# untitled.net
KiCad netlist of a schematic drawn in EAGLE
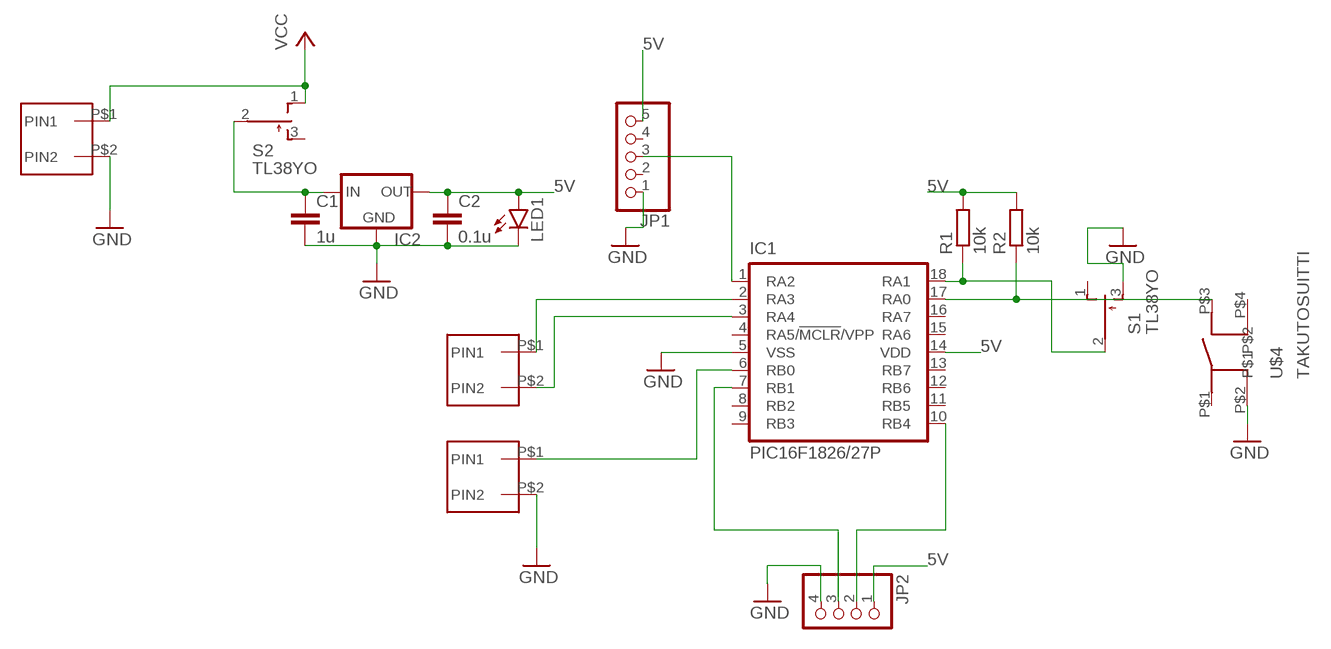
[diagram p0: schematic, sheet 1]

(export (version "E")
  (design (tool "Eeschema 10.0.6"))
  (components
    (comp (ref "C1")
      (value "1u")
      (footprint "eagle-import:C025-025X050")
      (libsource (lib "eagle-import") (part "C-EU025-025X050"))
    )
    (comp (ref "C2")
      (value "0.1u")
      (footprint "eagle-import:C025-025X050")
      (libsource (lib "eagle-import") (part "C-EU025-025X050"))
    )
    (comp (ref "IC1")
      (value "PIC16F1826/27P")
      (footprint "eagle-import:DIL18")
      (libsource (lib "eagle-import") (part "PIC16F1826/27P"))
    )
    (comp (ref "IC2")
      (value "78XXS")
      (footprint "eagle-import:78XXS")
      (libsource (lib "eagle-import") (part "78XXS"))
    )
    (comp (ref "JP1")
      (value "PINHD-1X5")
      (footprint "eagle-import:1X05")
      (libsource (lib "eagle-import") (part "PINHD-1X5"))
    )
    (comp (ref "JP2")
      (value "PINHD-1X4")
      (footprint "eagle-import:1X04")
      (libsource (lib "eagle-import") (part "PINHD-1X4"))
    )
    (comp (ref "LED1")
      (value "LED5MM")
      (footprint "eagle-import:LED5MM")
      (libsource (lib "eagle-import") (part "LED5MM"))
    )
    (comp (ref "R1")
      (value "10k")
      (footprint "eagle-import:0207_10")
      (libsource (lib "eagle-import") (part "R-EU_0207/10"))
    )
    (comp (ref "R2")
      (value "10k")
      (footprint "eagle-import:0207_10")
      (libsource (lib "eagle-import") (part "R-EU_0207/10"))
    )
    (comp (ref "S1")
      (value "TL38YO")
      (footprint "eagle-import:TL3XYO")
      (libsource (lib "eagle-import") (part "TL38YO"))
    )
    (comp (ref "S2")
      (value "TL38YO")
      (footprint "eagle-import:TL3XYO")
      (libsource (lib "eagle-import") (part "TL38YO"))
    )
    (comp (ref "U$1")
      (value "TERMINAL_2")
      (footprint "eagle-import:TERMINAL_2")
      (libsource (lib "eagle-import") (part "TERMINAL_2"))
    )
    (comp (ref "U$2")
      (value "TERMINAL_2")
      (footprint "eagle-import:TERMINAL_2")
      (libsource (lib "eagle-import") (part "TERMINAL_2"))
    )
    (comp (ref "U$3")
      (value "TERMINAL_2")
      (footprint "eagle-import:TERMINAL_2")
      (libsource (lib "eagle-import") (part "TERMINAL_2"))
    )
    (comp (ref "U$4")
      (value "TAKUTOSUITTI")
      (footprint "eagle-import:TAKUTOSUITTI")
      (libsource (lib "eagle-import") (part "TAKUTOSUITTI"))
    )
  )
  (nets
    (net (code "1") (name "/5V") (class "Default")
      (node (ref "C2") (pin "1") (pinfunction "1_1") (pintype "passive"))
      (node (ref "IC1") (pin "14") (pinfunction "VDD_14") (pintype "power_in"))
      (node (ref "IC2") (pin "OUT") (pinfunction "OUT_OUT") (pintype "passive"))
      (node (ref "JP1") (pin "5") (pinfunction "5_5") (pintype "passive"))
      (node (ref "JP2") (pin "1") (pinfunction "1_1") (pintype "passive"))
      (node (ref "LED1") (pin "A") (pinfunction "A_A") (pintype "passive"))
      (node (ref "R1") (pin "2") (pinfunction "2_2") (pintype "passive"))
      (node (ref "R2") (pin "2") (pinfunction "2_2") (pintype "passive"))
    )
    (net (code "2") (name "GND") (class "Default")
      (node (ref "C1") (pin "2") (pinfunction "2_2") (pintype "passive"))
      (node (ref "C2") (pin "2") (pinfunction "2_2") (pintype "passive"))
      (node (ref "IC1") (pin "5") (pinfunction "VSS_5") (pintype "power_in"))
      (node (ref "IC2") (pin "GND") (pinfunction "GND_GND") (pintype "input"))
      (node (ref "JP1") (pin "1") (pinfunction "1_1") (pintype "passive"))
      (node (ref "JP2") (pin "4") (pinfunction "4_4") (pintype "passive"))
      (node (ref "LED1") (pin "K") (pinfunction "C_K") (pintype "passive"))
      (node (ref "S1") (pin "3") (pinfunction "S_3") (pintype "passive"))
      (node (ref "U$1") (pin "P$2") (pinfunction "PIN2_P$2") (pintype "bidirectional"))
      (node (ref "U$3") (pin "P$2") (pinfunction "PIN2_P$2") (pintype "bidirectional"))
      (node (ref "U$4") (pin "P$2") (pinfunction "P$2_P$2") (pintype "bidirectional"))
    )
    (net (code "3") (name "Net-(IC1-RA0)") (class "Default")
      (node (ref "IC1") (pin "17") (pinfunction "RA0_17") (pintype "bidirectional"))
      (node (ref "R2") (pin "1") (pinfunction "1_1") (pintype "passive"))
      (node (ref "U$4") (pin "P$3") (pinfunction "S_P$3") (pintype "passive"))
    )
    (net (code "4") (name "Net-(IC1-RA1)") (class "Default")
      (node (ref "IC1") (pin "18") (pinfunction "RA1_18") (pintype "bidirectional"))
      (node (ref "R1") (pin "1") (pinfunction "1_1") (pintype "passive"))
      (node (ref "S1") (pin "2") (pinfunction "P_2") (pintype "passive"))
    )
    (net (code "5") (name "Net-(IC1-RA2)") (class "Default")
      (node (ref "IC1") (pin "1") (pinfunction "RA2_1") (pintype "bidirectional"))
      (node (ref "JP1") (pin "3") (pinfunction "3_3") (pintype "passive"))
    )
    (net (code "6") (name "Net-(IC1-RA3)") (class "Default")
      (node (ref "IC1") (pin "2") (pinfunction "RA3_2") (pintype "bidirectional"))
      (node (ref "U$2") (pin "P$1") (pinfunction "PIN1_P$1") (pintype "bidirectional"))
    )
    (net (code "7") (name "Net-(IC1-RA4)") (class "Default")
      (node (ref "IC1") (pin "3") (pinfunction "RA4_3") (pintype "bidirectional"))
      (node (ref "U$2") (pin "P$2") (pinfunction "PIN2_P$2") (pintype "bidirectional"))
    )
    (net (code "8") (name "Net-(IC1-RB0)") (class "Default")
      (node (ref "IC1") (pin "6") (pinfunction "RB0_6") (pintype "bidirectional"))
      (node (ref "U$3") (pin "P$1") (pinfunction "PIN1_P$1") (pintype "bidirectional"))
    )
    (net (code "9") (name "Net-(IC1-RB1)") (class "Default")
      (node (ref "IC1") (pin "7") (pinfunction "RB1_7") (pintype "bidirectional"))
      (node (ref "JP2") (pin "3") (pinfunction "3_3") (pintype "passive"))
    )
    (net (code "10") (name "Net-(IC1-RB4)") (class "Default")
      (node (ref "IC1") (pin "10") (pinfunction "RB4_10") (pintype "bidirectional"))
      (node (ref "JP2") (pin "2") (pinfunction "2_2") (pintype "passive"))
    )
    (net (code "11") (name "Net-(S2-P)") (class "Default")
      (node (ref "C1") (pin "1") (pinfunction "1_1") (pintype "passive"))
      (node (ref "IC2") (pin "IN") (pinfunction "IN_IN") (pintype "input"))
      (node (ref "S2") (pin "2") (pinfunction "P_2") (pintype "passive"))
    )
    (net (code "12") (name "VCC") (class "Default")
      (node (ref "S2") (pin "1") (pinfunction "O_1") (pintype "passive"))
      (node (ref "U$1") (pin "P$1") (pinfunction "PIN1_P$1") (pintype "bidirectional"))
    )
    (net (code "13") (name "unconnected-(IC1-RA5{slash}~{MCLR}{slash}VPP-Pad4)") (class "Default")
      (node (ref "IC1") (pin "4") (pinfunction "RA5/~{MCLR}/VPP_4") (pintype "bidirectional"))
    )
    (net (code "14") (name "unconnected-(IC1-RA6-Pad15)") (class "Default")
      (node (ref "IC1") (pin "15") (pinfunction "RA6_15") (pintype "bidirectional"))
    )
    (net (code "15") (name "unconnected-(IC1-RA7-Pad16)") (class "Default")
      (node (ref "IC1") (pin "16") (pinfunction "RA7_16") (pintype "bidirectional"))
    )
    (net (code "16") (name "unconnected-(IC1-RB2-Pad8)") (class "Default")
      (node (ref "IC1") (pin "8") (pinfunction "RB2_8") (pintype "bidirectional"))
    )
    (net (code "17") (name "unconnected-(IC1-RB3-Pad9)") (class "Default")
      (node (ref "IC1") (pin "9") (pinfunction "RB3_9") (pintype "bidirectional"))
    )
    (net (code "18") (name "unconnected-(IC1-RB5-Pad11)") (class "Default")
      (node (ref "IC1") (pin "11") (pinfunction "RB5_11") (pintype "bidirectional"))
    )
    (net (code "19") (name "unconnected-(IC1-RB6-Pad12)") (class "Default")
      (node (ref "IC1") (pin "12") (pinfunction "RB6_12") (pintype "bidirectional"))
    )
    (net (code "20") (name "unconnected-(IC1-RB7-Pad13)") (class "Default")
      (node (ref "IC1") (pin "13") (pinfunction "RB7_13") (pintype "bidirectional"))
    )
    (net (code "21") (name "unconnected-(JP1-Pad2)") (class "Default")
      (node (ref "JP1") (pin "2") (pinfunction "2_2") (pintype "passive"))
    )
    (net (code "22") (name "unconnected-(JP1-Pad4)") (class "Default")
      (node (ref "JP1") (pin "4") (pinfunction "4_4") (pintype "passive"))
    )
    (net (code "23") (name "unconnected-(S1-O-Pad1)") (class "Default")
      (node (ref "S1") (pin "1") (pinfunction "O_1") (pintype "passive"))
    )
    (net (code "24") (name "unconnected-(S2-S-Pad3)") (class "Default")
      (node (ref "S2") (pin "3") (pinfunction "S_3") (pintype "passive"))
    )
    (net (code "25") (name "unconnected-(U$4-P$1-PadP$4)") (class "Default")
      (node (ref "U$4") (pin "P$4") (pinfunction "P$1_P$4") (pintype "bidirectional"))
    )
    (net (code "26") (name "unconnected-(U$4-P-PadP$1)") (class "Default")
      (node (ref "U$4") (pin "P$1") (pinfunction "P_P$1") (pintype "passive"))
    )
  )
)
